# small.net
KiCad netlist of a schematic drawn in EAGLE
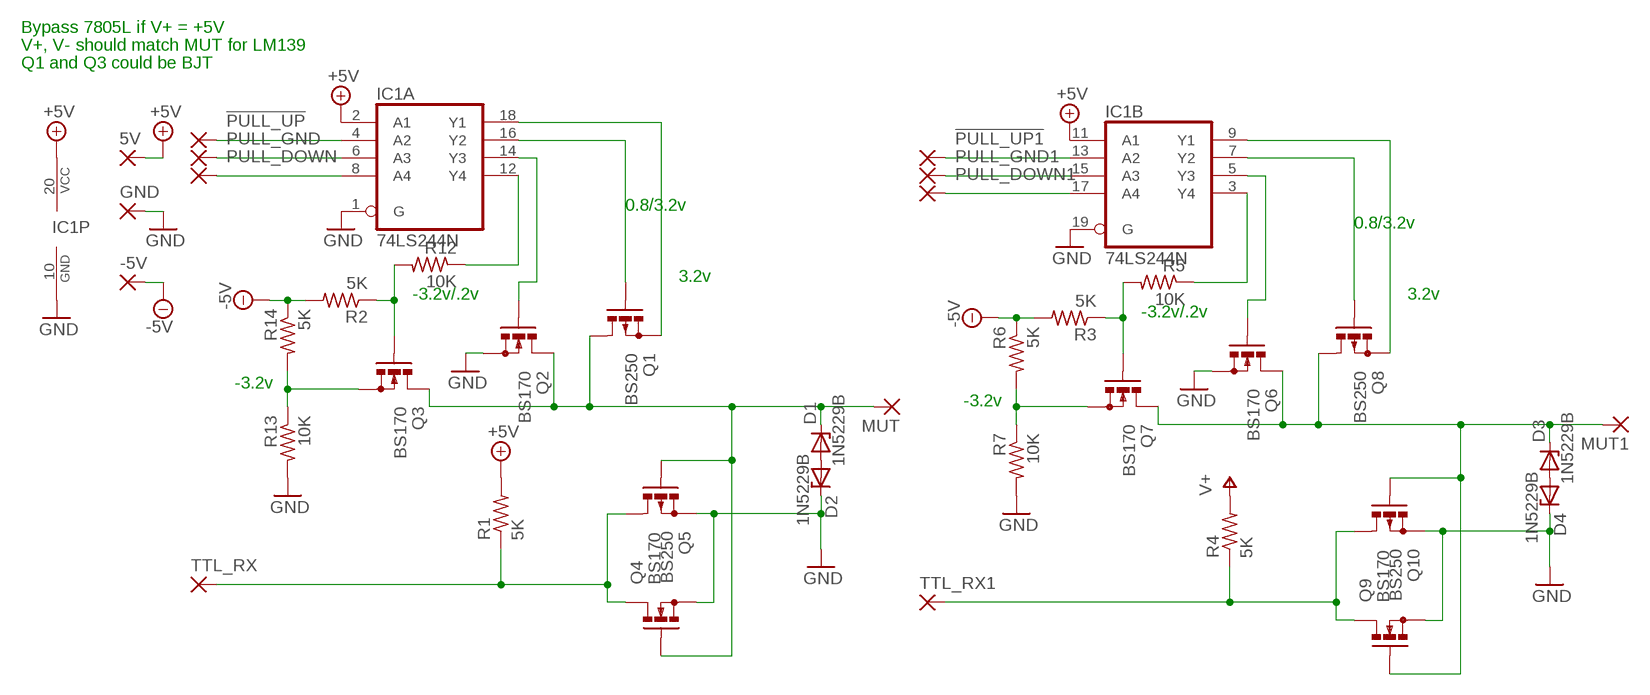
[diagram p0: schematic, sheet 1]

(export (version "E")
  (design (tool "Eeschema 10.0.6"))
  (components
    (comp (ref "!PULL_UP")
      (value "1,6/0,9")
      (footprint "eagle-import:1,6_0,9")
      (libsource (lib "eagle-import") (part "1,6/0,9"))
    )
    (comp (ref "!PULL_UP1")
      (value "1,6/0,9")
      (footprint "eagle-import:1,6_0,9")
      (libsource (lib "eagle-import") (part "1,6/0,9"))
    )
    (comp (ref "-5V")
      (value "1,6/0,9")
      (footprint "eagle-import:1,6_0,9")
      (libsource (lib "eagle-import") (part "1,6/0,9"))
    )
    (comp (ref "5V")
      (value "1,6/0,9")
      (footprint "eagle-import:1,6_0,9")
      (libsource (lib "eagle-import") (part "1,6/0,9"))
    )
    (comp (ref "D1")
      (value "1N5229B")
      (footprint "eagle-import:DO35Z10")
      (libsource (lib "eagle-import") (part "ZENER-DIODEDO35Z10"))
    )
    (comp (ref "D2")
      (value "1N5229B")
      (footprint "eagle-import:DO35Z10")
      (libsource (lib "eagle-import") (part "ZENER-DIODEDO35Z10"))
    )
    (comp (ref "D3")
      (value "1N5229B")
      (footprint "eagle-import:DO35Z10")
      (libsource (lib "eagle-import") (part "ZENER-DIODEDO35Z10"))
    )
    (comp (ref "D4")
      (value "1N5229B")
      (footprint "eagle-import:DO35Z10")
      (libsource (lib "eagle-import") (part "ZENER-DIODEDO35Z10"))
    )
    (comp (ref "GND")
      (value "1,6/0,9")
      (footprint "eagle-import:1,6_0,9")
      (libsource (lib "eagle-import") (part "1,6/0,9"))
    )
    (comp (ref "IC1")
      (value "74LS244N")
      (footprint "eagle-import:DIL20")
      (libsource (lib "eagle-import") (part "74244NLS"))
    )
    (comp (ref "MUT")
      (value "1,6/0,9")
      (footprint "eagle-import:1,6_0,9")
      (libsource (lib "eagle-import") (part "1,6/0,9"))
    )
    (comp (ref "MUT1")
      (value "1,6/0,9")
      (footprint "eagle-import:1,6_0,9")
      (libsource (lib "eagle-import") (part "1,6/0,9"))
    )
    (comp (ref "PULL_DOWN")
      (value "1,6/0,9")
      (footprint "eagle-import:1,6_0,9")
      (libsource (lib "eagle-import") (part "1,6/0,9"))
    )
    (comp (ref "PULL_DOWN1")
      (value "1,6/0,9")
      (footprint "eagle-import:1,6_0,9")
      (libsource (lib "eagle-import") (part "1,6/0,9"))
    )
    (comp (ref "PULL_GND")
      (value "1,6/0,9")
      (footprint "eagle-import:1,6_0,9")
      (libsource (lib "eagle-import") (part "1,6/0,9"))
    )
    (comp (ref "PULL_GND1")
      (value "1,6/0,9")
      (footprint "eagle-import:1,6_0,9")
      (libsource (lib "eagle-import") (part "1,6/0,9"))
    )
    (comp (ref "Q1")
      (value "BS250")
      (footprint "eagle-import:SOT54E")
      (libsource (lib "eagle-import") (part "BS250"))
    )
    (comp (ref "Q2")
      (value "BS170")
      (footprint "eagle-import:SOT54E")
      (libsource (lib "eagle-import") (part "BS170"))
    )
    (comp (ref "Q3")
      (value "BS170")
      (footprint "eagle-import:SOT54E")
      (libsource (lib "eagle-import") (part "BS170"))
    )
    (comp (ref "Q4")
      (value "BS170")
      (footprint "eagle-import:SOT54E")
      (libsource (lib "eagle-import") (part "BS170"))
    )
    (comp (ref "Q5")
      (value "BS250")
      (footprint "eagle-import:SOT54E")
      (libsource (lib "eagle-import") (part "BS250"))
    )
    (comp (ref "Q6")
      (value "BS170")
      (footprint "eagle-import:SOT54E")
      (libsource (lib "eagle-import") (part "BS170"))
    )
    (comp (ref "Q7")
      (value "BS170")
      (footprint "eagle-import:SOT54E")
      (libsource (lib "eagle-import") (part "BS170"))
    )
    (comp (ref "Q8")
      (value "BS250")
      (footprint "eagle-import:SOT54E")
      (libsource (lib "eagle-import") (part "BS250"))
    )
    (comp (ref "Q9")
      (value "BS170")
      (footprint "eagle-import:SOT54E")
      (libsource (lib "eagle-import") (part "BS170"))
    )
    (comp (ref "Q10")
      (value "BS250")
      (footprint "eagle-import:SOT54E")
      (libsource (lib "eagle-import") (part "BS250"))
    )
    (comp (ref "R1")
      (value "5K")
      (footprint "eagle-import:0207_10")
      (libsource (lib "eagle-import") (part "R-US_0207/10"))
    )
    (comp (ref "R2")
      (value "5K")
      (footprint "eagle-import:0207_10")
      (libsource (lib "eagle-import") (part "R-US_0207/10"))
    )
    (comp (ref "R3")
      (value "5K")
      (footprint "eagle-import:0207_10")
      (libsource (lib "eagle-import") (part "R-US_0207/10"))
    )
    (comp (ref "R4")
      (value "5K")
      (footprint "eagle-import:0207_10")
      (libsource (lib "eagle-import") (part "R-US_0207/10"))
    )
    (comp (ref "R5")
      (value "10K")
      (footprint "eagle-import:0207_10")
      (libsource (lib "eagle-import") (part "R-US_0207/10"))
    )
    (comp (ref "R6")
      (value "5K")
      (footprint "eagle-import:0207_10")
      (libsource (lib "eagle-import") (part "R-US_0207/10"))
    )
    (comp (ref "R7")
      (value "10K")
      (footprint "eagle-import:0207_10")
      (libsource (lib "eagle-import") (part "R-US_0207/10"))
    )
    (comp (ref "R12")
      (value "10K")
      (footprint "eagle-import:0207_10")
      (libsource (lib "eagle-import") (part "R-US_0207/10"))
    )
    (comp (ref "R13")
      (value "10K")
      (footprint "eagle-import:0207_10")
      (libsource (lib "eagle-import") (part "R-US_0207/10"))
    )
    (comp (ref "R14")
      (value "5K")
      (footprint "eagle-import:0207_10")
      (libsource (lib "eagle-import") (part "R-US_0207/10"))
    )
    (comp (ref "TTL_RX")
      (value "1,6/0,9")
      (footprint "eagle-import:1,6_0,9")
      (libsource (lib "eagle-import") (part "1,6/0,9"))
    )
    (comp (ref "TTL_RX1")
      (value "1,6/0,9")
      (footprint "eagle-import:1,6_0,9")
      (libsource (lib "eagle-import") (part "1,6/0,9"))
    )
  )
  (nets
    (net (code "1") (name "+5V") (class "Default")
      (node (ref "5V") (pin "1") (pinfunction "P_1") (pintype "passive"))
      (node (ref "IC1") (pin "11") (pinfunction "A1_11") (pintype "input"))
      (node (ref "IC1") (pin "2") (pinfunction "A1_2") (pintype "input"))
      (node (ref "IC1") (pin "20") (pinfunction "VCC_20") (pintype "power_in"))
      (node (ref "R1") (pin "2") (pinfunction "2_2") (pintype "passive"))
    )
    (net (code "2") (name "-5V") (class "Default")
      (node (ref "-5V") (pin "1") (pinfunction "P_1") (pintype "passive"))
      (node (ref "R14") (pin "1") (pinfunction "1_1") (pintype "passive"))
      (node (ref "R2") (pin "2") (pinfunction "2_2") (pintype "passive"))
      (node (ref "R3") (pin "2") (pinfunction "2_2") (pintype "passive"))
      (node (ref "R6") (pin "1") (pinfunction "1_1") (pintype "passive"))
    )
    (net (code "3") (name "GND") (class "Default")
      (node (ref "D2") (pin "C") (pinfunction "C_C") (pintype "passive"))
      (node (ref "D4") (pin "C") (pinfunction "C_C") (pintype "passive"))
      (node (ref "GND") (pin "1") (pinfunction "P_1") (pintype "passive"))
      (node (ref "IC1") (pin "1") (pinfunction "G_1") (pintype "input"))
      (node (ref "IC1") (pin "10") (pinfunction "GND_10") (pintype "power_in"))
      (node (ref "IC1") (pin "19") (pinfunction "G_19") (pintype "input"))
      (node (ref "Q10") (pin "S") (pinfunction "S_S") (pintype "passive"))
      (node (ref "Q2") (pin "S") (pinfunction "S_S") (pintype "passive"))
      (node (ref "Q4") (pin "S") (pinfunction "S_S") (pintype "passive"))
      (node (ref "Q5") (pin "S") (pinfunction "S_S") (pintype "passive"))
      (node (ref "Q6") (pin "S") (pinfunction "S_S") (pintype "passive"))
      (node (ref "Q9") (pin "S") (pinfunction "S_S") (pintype "passive"))
      (node (ref "R13") (pin "2") (pinfunction "2_2") (pintype "passive"))
      (node (ref "R7") (pin "2") (pinfunction "2_2") (pintype "passive"))
    )
    (net (code "4") (name "Net-(!PULL_UP-P)") (class "Default")
      (node (ref "!PULL_UP") (pin "1") (pinfunction "P_1") (pintype "passive"))
      (node (ref "IC1") (pin "4") (pinfunction "A2_4") (pintype "input"))
    )
    (net (code "5") (name "Net-(!PULL_UP1-P)") (class "Default")
      (node (ref "!PULL_UP1") (pin "1") (pinfunction "P_1") (pintype "passive"))
      (node (ref "IC1") (pin "13") (pinfunction "A2_13") (pintype "input"))
    )
    (net (code "6") (name "Net-(D1-PadA)") (class "Default")
      (node (ref "D1") (pin "A") (pinfunction "A_A") (pintype "passive"))
      (node (ref "D2") (pin "A") (pinfunction "A_A") (pintype "passive"))
    )
    (net (code "7") (name "Net-(D3-PadA)") (class "Default")
      (node (ref "D3") (pin "A") (pinfunction "A_A") (pintype "passive"))
      (node (ref "D4") (pin "A") (pinfunction "A_A") (pintype "passive"))
    )
    (net (code "8") (name "Net-(IC1A-A3)") (class "Default")
      (node (ref "IC1") (pin "6") (pinfunction "A3_6") (pintype "input"))
      (node (ref "PULL_GND") (pin "1") (pinfunction "P_1") (pintype "passive"))
    )
    (net (code "9") (name "Net-(IC1A-A4)") (class "Default")
      (node (ref "IC1") (pin "8") (pinfunction "A4_8") (pintype "input"))
      (node (ref "PULL_DOWN") (pin "1") (pinfunction "P_1") (pintype "passive"))
    )
    (net (code "10") (name "Net-(IC1A-Y1)") (class "Default")
      (node (ref "IC1") (pin "18") (pinfunction "Y1_18") (pintype "tri_state"))
      (node (ref "Q1") (pin "S") (pinfunction "S_S") (pintype "passive"))
    )
    (net (code "11") (name "Net-(IC1A-Y2)") (class "Default")
      (node (ref "IC1") (pin "16") (pinfunction "Y2_16") (pintype "tri_state"))
      (node (ref "Q1") (pin "G") (pinfunction "G_G") (pintype "passive"))
    )
    (net (code "12") (name "Net-(IC1A-Y3)") (class "Default")
      (node (ref "IC1") (pin "14") (pinfunction "Y3_14") (pintype "tri_state"))
      (node (ref "Q2") (pin "G") (pinfunction "G_G") (pintype "passive"))
    )
    (net (code "13") (name "Net-(IC1A-Y4)") (class "Default")
      (node (ref "IC1") (pin "12") (pinfunction "Y4_12") (pintype "tri_state"))
      (node (ref "R12") (pin "1") (pinfunction "1_1") (pintype "passive"))
    )
    (net (code "14") (name "Net-(IC1B-A3)") (class "Default")
      (node (ref "IC1") (pin "15") (pinfunction "A3_15") (pintype "input"))
      (node (ref "PULL_GND1") (pin "1") (pinfunction "P_1") (pintype "passive"))
    )
    (net (code "15") (name "Net-(IC1B-A4)") (class "Default")
      (node (ref "IC1") (pin "17") (pinfunction "A4_17") (pintype "input"))
      (node (ref "PULL_DOWN1") (pin "1") (pinfunction "P_1") (pintype "passive"))
    )
    (net (code "16") (name "Net-(IC1B-Y1)") (class "Default")
      (node (ref "IC1") (pin "9") (pinfunction "Y1_9") (pintype "tri_state"))
      (node (ref "Q8") (pin "S") (pinfunction "S_S") (pintype "passive"))
    )
    (net (code "17") (name "Net-(IC1B-Y2)") (class "Default")
      (node (ref "IC1") (pin "7") (pinfunction "Y2_7") (pintype "tri_state"))
      (node (ref "Q8") (pin "G") (pinfunction "G_G") (pintype "passive"))
    )
    (net (code "18") (name "Net-(IC1B-Y3)") (class "Default")
      (node (ref "IC1") (pin "5") (pinfunction "Y3_5") (pintype "tri_state"))
      (node (ref "Q6") (pin "G") (pinfunction "G_G") (pintype "passive"))
    )
    (net (code "19") (name "Net-(IC1B-Y4)") (class "Default")
      (node (ref "IC1") (pin "3") (pinfunction "Y4_3") (pintype "tri_state"))
      (node (ref "R5") (pin "1") (pinfunction "1_1") (pintype "passive"))
    )
    (net (code "20") (name "Net-(MUT-P)") (class "Default")
      (node (ref "D1") (pin "C") (pinfunction "C_C") (pintype "passive"))
      (node (ref "MUT") (pin "1") (pinfunction "P_1") (pintype "passive"))
      (node (ref "Q1") (pin "D") (pinfunction "D_D") (pintype "passive"))
      (node (ref "Q2") (pin "D") (pinfunction "D_D") (pintype "passive"))
      (node (ref "Q3") (pin "D") (pinfunction "D_D") (pintype "passive"))
      (node (ref "Q4") (pin "G") (pinfunction "G_G") (pintype "passive"))
      (node (ref "Q5") (pin "G") (pinfunction "G_G") (pintype "passive"))
    )
    (net (code "21") (name "Net-(MUT1-P)") (class "Default")
      (node (ref "D3") (pin "C") (pinfunction "C_C") (pintype "passive"))
      (node (ref "MUT1") (pin "1") (pinfunction "P_1") (pintype "passive"))
      (node (ref "Q10") (pin "G") (pinfunction "G_G") (pintype "passive"))
      (node (ref "Q6") (pin "D") (pinfunction "D_D") (pintype "passive"))
      (node (ref "Q7") (pin "D") (pinfunction "D_D") (pintype "passive"))
      (node (ref "Q8") (pin "D") (pinfunction "D_D") (pintype "passive"))
      (node (ref "Q9") (pin "G") (pinfunction "G_G") (pintype "passive"))
    )
    (net (code "22") (name "Net-(Q3-PadG)") (class "Default")
      (node (ref "Q3") (pin "G") (pinfunction "G_G") (pintype "passive"))
      (node (ref "R12") (pin "2") (pinfunction "2_2") (pintype "passive"))
      (node (ref "R2") (pin "1") (pinfunction "1_1") (pintype "passive"))
    )
    (net (code "23") (name "Net-(Q3-PadS)") (class "Default")
      (node (ref "Q3") (pin "S") (pinfunction "S_S") (pintype "passive"))
      (node (ref "R13") (pin "1") (pinfunction "1_1") (pintype "passive"))
      (node (ref "R14") (pin "2") (pinfunction "2_2") (pintype "passive"))
    )
    (net (code "24") (name "Net-(Q7-PadG)") (class "Default")
      (node (ref "Q7") (pin "G") (pinfunction "G_G") (pintype "passive"))
      (node (ref "R3") (pin "1") (pinfunction "1_1") (pintype "passive"))
      (node (ref "R5") (pin "2") (pinfunction "2_2") (pintype "passive"))
    )
    (net (code "25") (name "Net-(Q7-PadS)") (class "Default")
      (node (ref "Q7") (pin "S") (pinfunction "S_S") (pintype "passive"))
      (node (ref "R6") (pin "2") (pinfunction "2_2") (pintype "passive"))
      (node (ref "R7") (pin "1") (pinfunction "1_1") (pintype "passive"))
    )
    (net (code "26") (name "Net-(TTL_RX-P)") (class "Default")
      (node (ref "Q4") (pin "D") (pinfunction "D_D") (pintype "passive"))
      (node (ref "Q5") (pin "D") (pinfunction "D_D") (pintype "passive"))
      (node (ref "R1") (pin "1") (pinfunction "1_1") (pintype "passive"))
      (node (ref "TTL_RX") (pin "1") (pinfunction "P_1") (pintype "passive"))
    )
    (net (code "27") (name "Net-(TTL_RX1-P)") (class "Default")
      (node (ref "Q10") (pin "D") (pinfunction "D_D") (pintype "passive"))
      (node (ref "Q9") (pin "D") (pinfunction "D_D") (pintype "passive"))
      (node (ref "R4") (pin "1") (pinfunction "1_1") (pintype "passive"))
      (node (ref "TTL_RX1") (pin "1") (pinfunction "P_1") (pintype "passive"))
    )
    (net (code "28") (name "V+") (class "Default")
      (node (ref "R4") (pin "2") (pinfunction "2_2") (pintype "passive"))
    )
  )
)
